# L_ftersteuerung.net
KiCad netlist of a schematic drawn in EAGLE
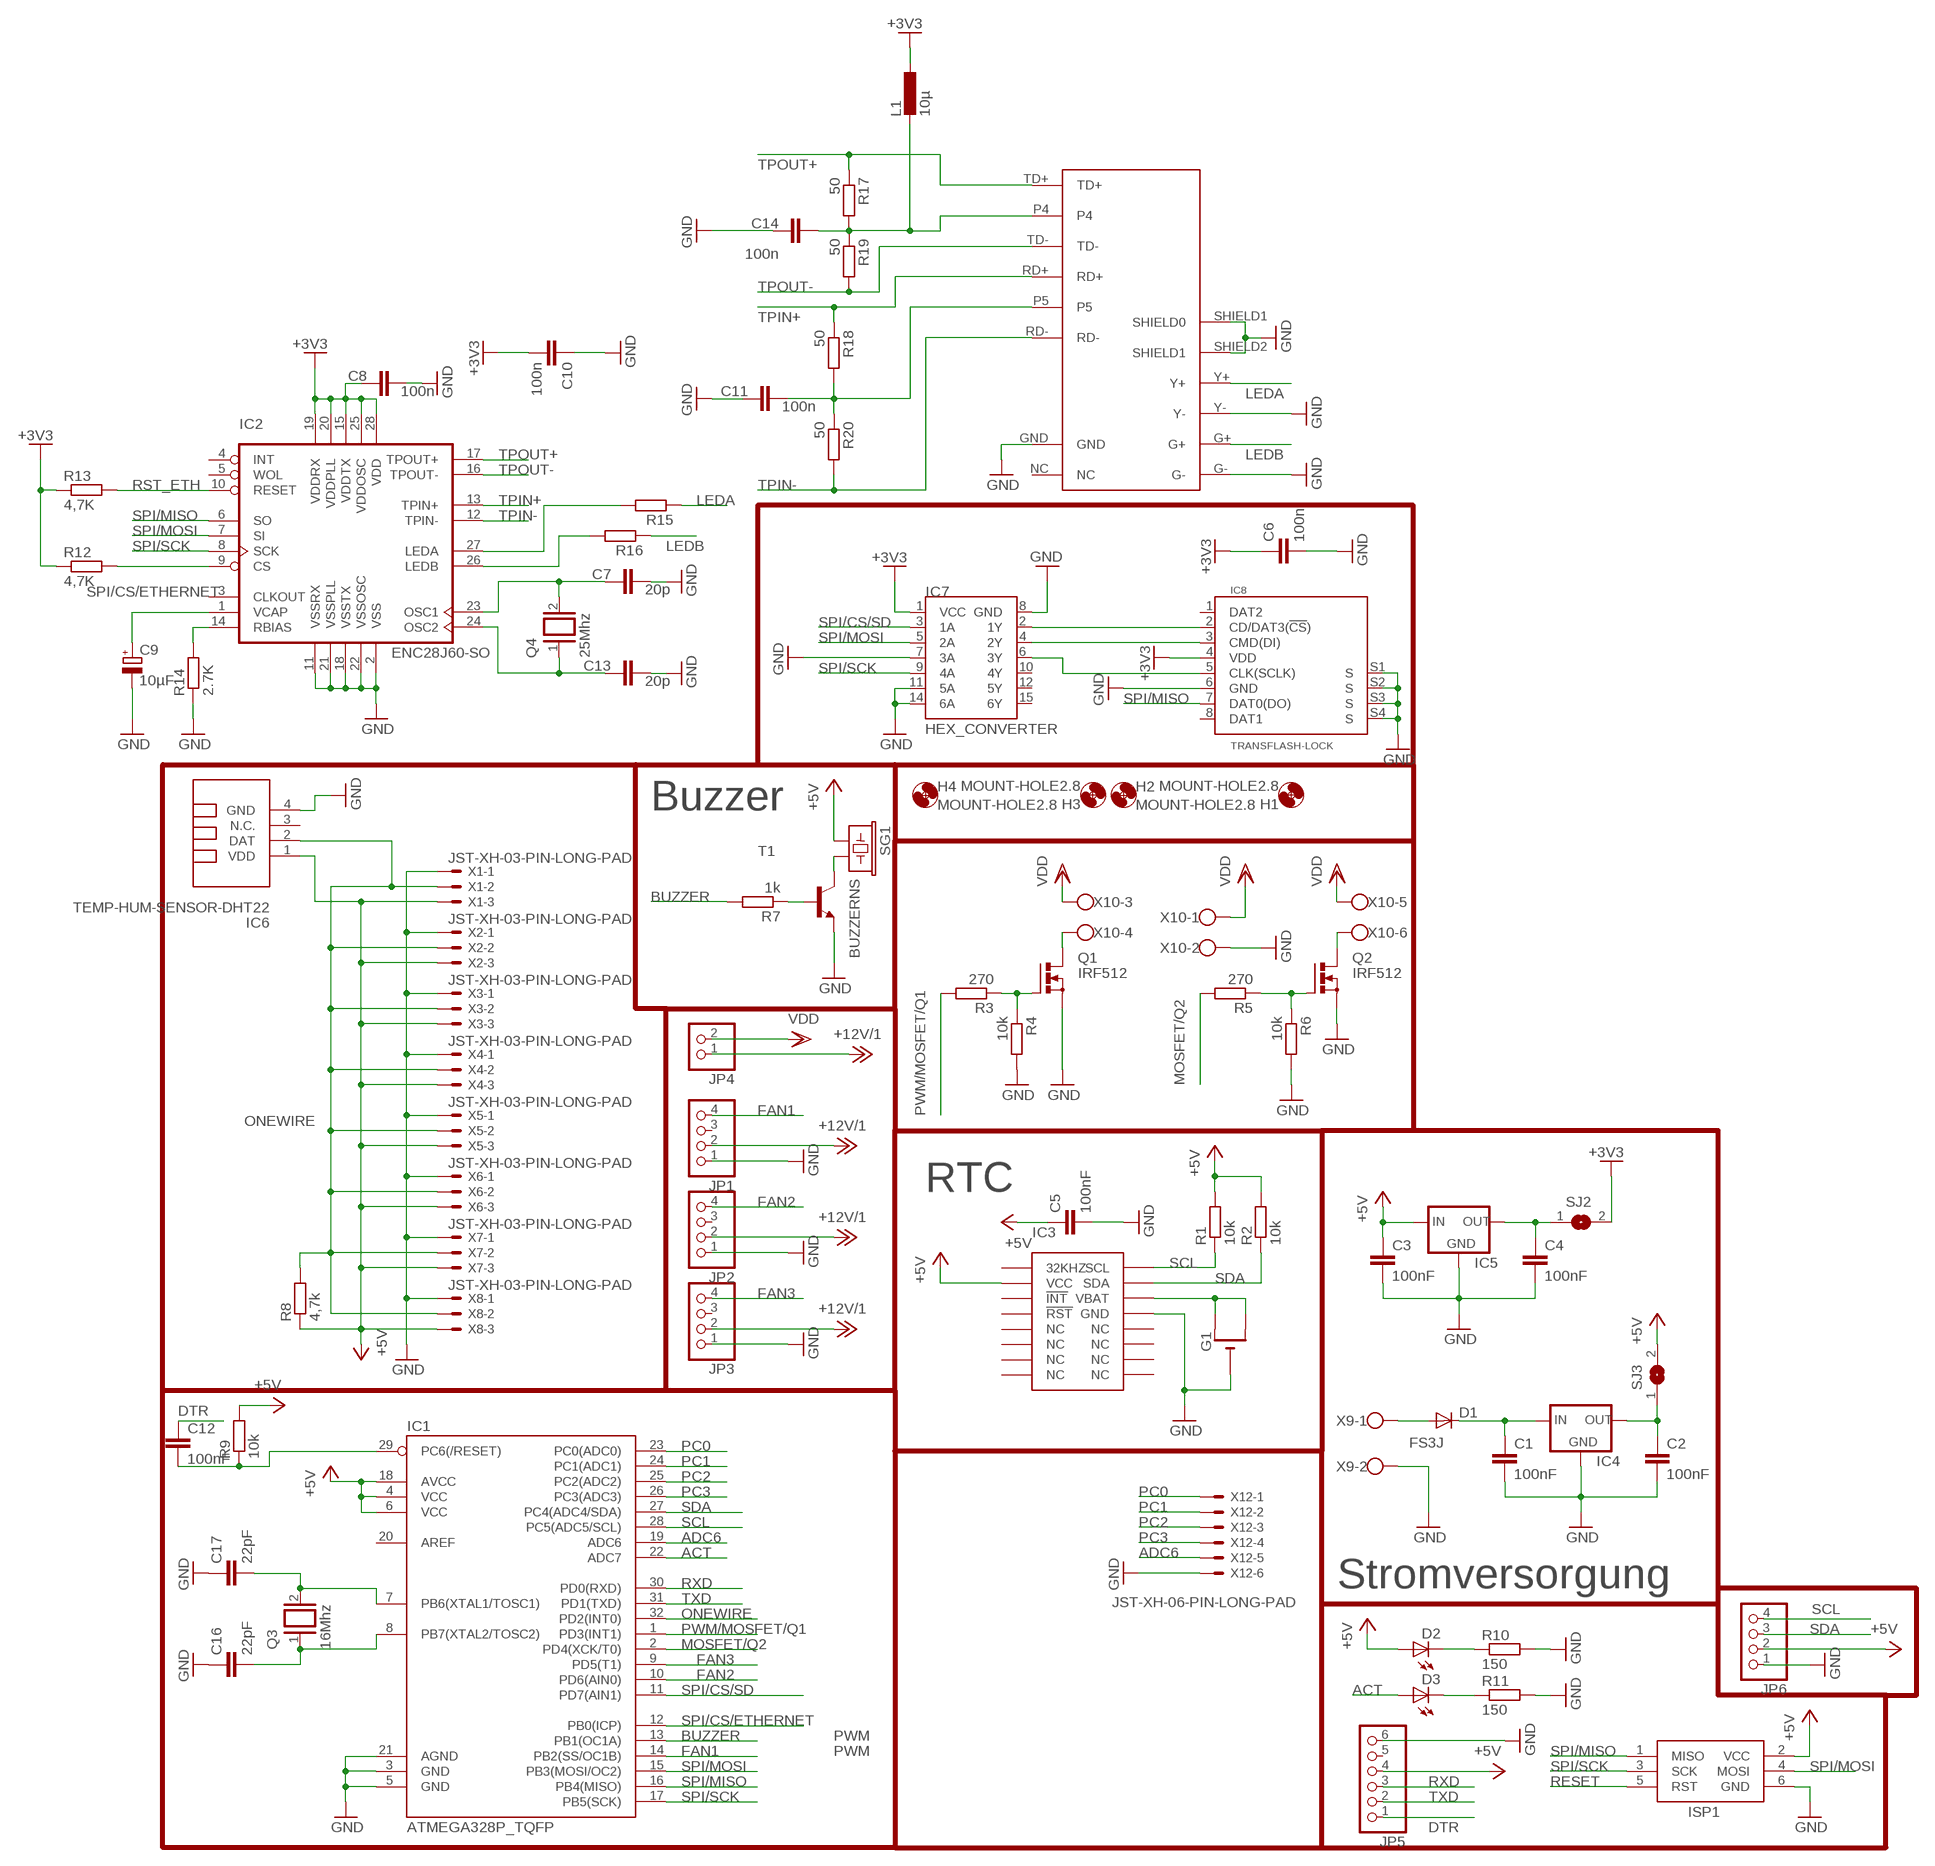
[diagram p0: schematic, sheet 1]

(export (version "E")
  (design (tool "Eeschema 10.0.6"))
  (components
    (comp (ref "C1")
      (value "100nF")
      (footprint "eagle-import:C1206")
      (libsource (lib "eagle-import") (part "C-EUC1206"))
    )
    (comp (ref "C2")
      (value "100nF")
      (footprint "eagle-import:C1206")
      (libsource (lib "eagle-import") (part "C-EUC1206"))
    )
    (comp (ref "C3")
      (value "100nF")
      (footprint "eagle-import:C1206")
      (libsource (lib "eagle-import") (part "C-EUC1206"))
    )
    (comp (ref "C4")
      (value "100nF")
      (footprint "eagle-import:C1206")
      (libsource (lib "eagle-import") (part "C-EUC1206"))
    )
    (comp (ref "C5")
      (value "100nF")
      (footprint "eagle-import:C1206")
      (libsource (lib "eagle-import") (part "C-EUC1206"))
    )
    (comp (ref "C6")
      (value "100n")
      (footprint "eagle-import:C1206")
      (libsource (lib "eagle-import") (part "C-EUC1206"))
    )
    (comp (ref "C7")
      (value "20p")
      (footprint "eagle-import:C1206")
      (libsource (lib "eagle-import") (part "C-EUC1206"))
    )
    (comp (ref "C8")
      (value "100n")
      (footprint "eagle-import:C1206")
      (libsource (lib "eagle-import") (part "C-EUC1206"))
    )
    (comp (ref "C9")
      (value "10µF")
      (footprint "eagle-import:A_3216-18W")
      (libsource (lib "eagle-import") (part "CPOL-EUA/3216-18W"))
    )
    (comp (ref "C10")
      (value "100n")
      (footprint "eagle-import:C1206")
      (libsource (lib "eagle-import") (part "C-EUC1206"))
    )
    (comp (ref "C11")
      (value "100n")
      (footprint "eagle-import:C1206")
      (libsource (lib "eagle-import") (part "C-EUC1206"))
    )
    (comp (ref "C12")
      (value "100nF")
      (footprint "eagle-import:C1206K")
      (libsource (lib "eagle-import") (part "C-EUC1206K"))
    )
    (comp (ref "C13")
      (value "20p")
      (footprint "eagle-import:C1206")
      (libsource (lib "eagle-import") (part "C-EUC1206"))
    )
    (comp (ref "C14")
      (value "100n")
      (footprint "eagle-import:C1206")
      (libsource (lib "eagle-import") (part "C-EUC1206"))
    )
    (comp (ref "C16")
      (value "22pF")
      (footprint "eagle-import:C1206K")
      (libsource (lib "eagle-import") (part "C-EUC1206K"))
    )
    (comp (ref "C17")
      (value "22pF")
      (footprint "eagle-import:C1206K")
      (libsource (lib "eagle-import") (part "C-EUC1206K"))
    )
    (comp (ref "D1")
      (value "FS3J")
      (footprint "eagle-import:SMC")
      (libsource (lib "eagle-import") (part "DIODE-SMC"))
    )
    (comp (ref "D2")
      (value "LED3MM")
      (footprint "eagle-import:LED3MM")
      (libsource (lib "eagle-import") (part "LED3MM"))
    )
    (comp (ref "D3")
      (value "LED3MM")
      (footprint "eagle-import:LED3MM")
      (libsource (lib "eagle-import") (part "LED3MM"))
    )
    (comp (ref "G1")
      (value "CR1220SMT")
      (footprint "eagle-import:CR1220-SMD")
      (libsource (lib "eagle-import") (part "CR1220SMT"))
    )
    (comp (ref "H1")
      (value "MOUNT-HOLE2.8")
      (footprint "eagle-import:2,8")
      (libsource (lib "eagle-import") (part "MOUNT-HOLE2.8"))
    )
    (comp (ref "H2")
      (value "MOUNT-HOLE2.8")
      (footprint "eagle-import:2,8")
      (libsource (lib "eagle-import") (part "MOUNT-HOLE2.8"))
    )
    (comp (ref "H3")
      (value "MOUNT-HOLE2.8")
      (footprint "eagle-import:2,8")
      (libsource (lib "eagle-import") (part "MOUNT-HOLE2.8"))
    )
    (comp (ref "H4")
      (value "MOUNT-HOLE2.8")
      (footprint "eagle-import:2,8")
      (libsource (lib "eagle-import") (part "MOUNT-HOLE2.8"))
    )
    (comp (ref "IC1")
      (value "ATMEGA328P_TQFP")
      (footprint "eagle-import:TQFP32-08")
      (libsource (lib "eagle-import") (part "ATMEGA328P_TQFP"))
    )
    (comp (ref "IC2")
      (value "ENC28J60-SO")
      (footprint "eagle-import:SO28W")
      (libsource (lib "eagle-import") (part "ENC28J60-SO"))
    )
    (comp (ref "IC3")
      (value "DS3231SOIC-16W")
      (footprint "eagle-import:SOIC-16W")
      (libsource (lib "eagle-import") (part "DS3231SOIC-16W"))
    )
    (comp (ref "IC4")
      (value "LM1117")
      (footprint "eagle-import:SOT223")
      (libsource (lib "eagle-import") (part "LM1117"))
    )
    (comp (ref "IC5")
      (value "LM1117")
      (footprint "eagle-import:SOT223")
      (libsource (lib "eagle-import") (part "LM1117"))
    )
    (comp (ref "IC6")
      (value "TEMP-HUM-SENSOR-DHT22")
      (footprint "eagle-import:TEMP-HUM-SENSOR-DHT22")
      (libsource (lib "eagle-import") (part "TEMP-HUM-SENSOR-DHT22"))
    )
    (comp (ref "IC7")
      (value "HEX_CONVERTER")
      (footprint "eagle-import:SO016")
      (libsource (lib "eagle-import") (part "HEX_CONVERTER"))
    )
    (comp (ref "IC8")
      (value "TRANSFLASH-LOCK")
      (footprint "eagle-import:TRANSFLASH-LOCK-SOCK")
      (libsource (lib "eagle-import") (part "TRANSFLASH-LOCK"))
    )
    (comp (ref "ISP1")
      (value "AVRISP-6")
      (footprint "eagle-import:AVRISP")
      (libsource (lib "eagle-import") (part "AVRISP-6"))
    )
    (comp (ref "JP1")
      (value "PINHD-1X4")
      (footprint "eagle-import:1X04")
      (libsource (lib "eagle-import") (part "PINHD-1X4"))
    )
    (comp (ref "JP2")
      (value "PINHD-1X4")
      (footprint "eagle-import:1X04")
      (libsource (lib "eagle-import") (part "PINHD-1X4"))
    )
    (comp (ref "JP3")
      (value "PINHD-1X4")
      (footprint "eagle-import:1X04")
      (libsource (lib "eagle-import") (part "PINHD-1X4"))
    )
    (comp (ref "JP4")
      (value "PINHD-1X2")
      (footprint "eagle-import:1X02")
      (libsource (lib "eagle-import") (part "PINHD-1X2"))
    )
    (comp (ref "JP5")
      (value "PINHD-1X6")
      (footprint "eagle-import:1X06")
      (libsource (lib "eagle-import") (part "PINHD-1X6"))
    )
    (comp (ref "JP6")
      (value "PINHD-1X4")
      (footprint "eagle-import:1X04")
      (libsource (lib "eagle-import") (part "PINHD-1X4"))
    )
    (comp (ref "L1")
      (value "10µ")
      (footprint "eagle-import:L0805")
      (libsource (lib "eagle-import") (part "L-EUL0805"))
    )
    (comp (ref "Q1")
      (value "IRF512")
      (footprint "eagle-import:TO220BV")
      (libsource (lib "eagle-import") (part "IRF512"))
    )
    (comp (ref "Q2")
      (value "IRF512")
      (footprint "eagle-import:TO220BV")
      (libsource (lib "eagle-import") (part "IRF512"))
    )
    (comp (ref "Q3")
      (value "16Mhz")
      (footprint "eagle-import:QS")
      (libsource (lib "eagle-import") (part "XTAL/S"))
    )
    (comp (ref "Q4")
      (value "25Mhz")
      (footprint "eagle-import:QS")
      (libsource (lib "eagle-import") (part "XTAL/S"))
    )
    (comp (ref "R1")
      (value "10k")
      (footprint "eagle-import:R1206")
      (libsource (lib "eagle-import") (part "R-EU_R1206"))
    )
    (comp (ref "R2")
      (value "10k")
      (footprint "eagle-import:R1206")
      (libsource (lib "eagle-import") (part "R-EU_R1206"))
    )
    (comp (ref "R3")
      (value "270")
      (footprint "eagle-import:R1206")
      (libsource (lib "eagle-import") (part "R-EU_R1206"))
    )
    (comp (ref "R4")
      (value "10k")
      (footprint "eagle-import:R1206")
      (libsource (lib "eagle-import") (part "R-EU_R1206"))
    )
    (comp (ref "R5")
      (value "270")
      (footprint "eagle-import:R1206")
      (libsource (lib "eagle-import") (part "R-EU_R1206"))
    )
    (comp (ref "R6")
      (value "10k")
      (footprint "eagle-import:R1206")
      (libsource (lib "eagle-import") (part "R-EU_R1206"))
    )
    (comp (ref "R7")
      (value "1k")
      (footprint "eagle-import:R1206")
      (libsource (lib "eagle-import") (part "R-EU_R1206"))
    )
    (comp (ref "R8")
      (value "4,7k")
      (footprint "eagle-import:R1206")
      (libsource (lib "eagle-import") (part "R-EU_R1206"))
    )
    (comp (ref "R9")
      (value "10k")
      (footprint "eagle-import:M1206")
      (libsource (lib "eagle-import") (part "R-EU_M1206"))
    )
    (comp (ref "R10")
      (value "150")
      (footprint "eagle-import:M1206")
      (libsource (lib "eagle-import") (part "R-EU_M1206"))
    )
    (comp (ref "R11")
      (value "150")
      (footprint "eagle-import:M1206")
      (libsource (lib "eagle-import") (part "R-EU_M1206"))
    )
    (comp (ref "R12")
      (value "4,7K")
      (footprint "eagle-import:R1206")
      (libsource (lib "eagle-import") (part "R-EU_R1206"))
    )
    (comp (ref "R13")
      (value "4,7K")
      (footprint "eagle-import:R1206")
      (libsource (lib "eagle-import") (part "R-EU_R1206"))
    )
    (comp (ref "R14")
      (value "2.7K")
      (footprint "eagle-import:R1206")
      (libsource (lib "eagle-import") (part "R-EU_R1206"))
    )
    (comp (ref "R15")
      (value "R-EU_R1206")
      (footprint "eagle-import:R1206")
      (libsource (lib "eagle-import") (part "R-EU_R1206"))
    )
    (comp (ref "R16")
      (value "R-EU_R1206")
      (footprint "eagle-import:R1206")
      (libsource (lib "eagle-import") (part "R-EU_R1206"))
    )
    (comp (ref "R17")
      (value "50")
      (footprint "eagle-import:R1206")
      (libsource (lib "eagle-import") (part "R-EU_R1206"))
    )
    (comp (ref "R18")
      (value "50")
      (footprint "eagle-import:R1206")
      (libsource (lib "eagle-import") (part "R-EU_R1206"))
    )
    (comp (ref "R19")
      (value "50")
      (footprint "eagle-import:R1206")
      (libsource (lib "eagle-import") (part "R-EU_R1206"))
    )
    (comp (ref "R20")
      (value "50")
      (footprint "eagle-import:R1206")
      (libsource (lib "eagle-import") (part "R-EU_R1206"))
    )
    (comp (ref "SG1")
      (value "BUZZERNS")
      (footprint "eagle-import:BUZZER-12MM-NS")
      (libsource (lib "eagle-import") (part "BUZZERNS"))
    )
    (comp (ref "SJ2") (value "SJ") (footprint "eagle-import:SJ") (libsource (lib "eagle-import") (part "SJ")))
    (comp (ref "SJ3") (value "SJ") (footprint "eagle-import:SJ") (libsource (lib "eagle-import") (part "SJ")))
    (comp (ref "T1")
      (value "BC817-16-NPN-SOT23-BEC")
      (footprint "eagle-import:SOT23-BEC")
      (libsource (lib "eagle-import") (part "-NPN-SOT23-BECBC817-16"))
    )
    (comp (ref "U$1")
      (value "HR911105A")
      (footprint "eagle-import:RJ45")
      (libsource (lib "eagle-import") (part "HR911105A"))
    )
    (comp (ref "X1")
      (value "JST-XH-03-PIN-LONG-PAD")
      (footprint "eagle-import:JST-XH-03-PACKAGE-LONG-PAD")
      (libsource (lib "eagle-import") (part "JST-XH-03-PIN-LONG-PAD"))
    )
    (comp (ref "X2")
      (value "JST-XH-03-PIN-LONG-PAD")
      (footprint "eagle-import:JST-XH-03-PACKAGE-LONG-PAD")
      (libsource (lib "eagle-import") (part "JST-XH-03-PIN-LONG-PAD"))
    )
    (comp (ref "X3")
      (value "JST-XH-03-PIN-LONG-PAD")
      (footprint "eagle-import:JST-XH-03-PACKAGE-LONG-PAD")
      (libsource (lib "eagle-import") (part "JST-XH-03-PIN-LONG-PAD"))
    )
    (comp (ref "X4")
      (value "JST-XH-03-PIN-LONG-PAD")
      (footprint "eagle-import:JST-XH-03-PACKAGE-LONG-PAD")
      (libsource (lib "eagle-import") (part "JST-XH-03-PIN-LONG-PAD"))
    )
    (comp (ref "X5")
      (value "JST-XH-03-PIN-LONG-PAD")
      (footprint "eagle-import:JST-XH-03-PACKAGE-LONG-PAD")
      (libsource (lib "eagle-import") (part "JST-XH-03-PIN-LONG-PAD"))
    )
    (comp (ref "X6")
      (value "JST-XH-03-PIN-LONG-PAD")
      (footprint "eagle-import:JST-XH-03-PACKAGE-LONG-PAD")
      (libsource (lib "eagle-import") (part "JST-XH-03-PIN-LONG-PAD"))
    )
    (comp (ref "X7")
      (value "JST-XH-03-PIN-LONG-PAD")
      (footprint "eagle-import:JST-XH-03-PACKAGE-LONG-PAD")
      (libsource (lib "eagle-import") (part "JST-XH-03-PIN-LONG-PAD"))
    )
    (comp (ref "X8")
      (value "JST-XH-03-PIN-LONG-PAD")
      (footprint "eagle-import:JST-XH-03-PACKAGE-LONG-PAD")
      (libsource (lib "eagle-import") (part "JST-XH-03-PIN-LONG-PAD"))
    )
    (comp (ref "X9")
      (value "W237-102")
      (footprint "eagle-import:W237-102")
      (libsource (lib "eagle-import") (part "W237-102"))
    )
    (comp (ref "X10")
      (value "W237-6")
      (footprint "eagle-import:W237-6")
      (libsource (lib "eagle-import") (part "W237-6"))
    )
    (comp (ref "X12")
      (value "JST-XH-06-PIN-LONG-PAD")
      (footprint "eagle-import:JST-XH-06-PACKAGE-LONG-PAD")
      (libsource (lib "eagle-import") (part "JST-XH-06-PIN-LONG-PAD"))
    )
  )
  (nets
    (net (code "1") (name "+3V3") (class "Default")
      (node (ref "C10") (pin "2") (pinfunction "2_2") (pintype "passive"))
      (node (ref "C6") (pin "1") (pinfunction "1_1") (pintype "passive"))
      (node (ref "C8") (pin "1") (pinfunction "1_1") (pintype "passive"))
      (node (ref "IC2") (pin "15") (pinfunction "VDDTX_15") (pintype "power_in"))
      (node (ref "IC2") (pin "19") (pinfunction "VDDRX_19") (pintype "power_in"))
      (node (ref "IC2") (pin "20") (pinfunction "VDDPLL_20") (pintype "power_in"))
      (node (ref "IC2") (pin "25") (pinfunction "VDDOSC_25") (pintype "power_in"))
      (node (ref "IC2") (pin "28") (pinfunction "VDD_28") (pintype "power_in"))
      (node (ref "IC7") (pin "1") (pinfunction "VCC_1") (pintype "bidirectional"))
      (node (ref "IC8") (pin "4") (pinfunction "VDD_4") (pintype "power_in"))
      (node (ref "L1") (pin "1") (pinfunction "1_1") (pintype "passive"))
      (node (ref "R12") (pin "1") (pinfunction "1_1") (pintype "passive"))
      (node (ref "R13") (pin "1") (pinfunction "1_1") (pintype "passive"))
      (node (ref "SJ2") (pin "2") (pinfunction "2_2") (pintype "passive"))
    )
    (net (code "2") (name "+5V") (class "Default")
      (node (ref "C3") (pin "1") (pinfunction "1_1") (pintype "passive"))
      (node (ref "C5") (pin "1") (pinfunction "1_1") (pintype "passive"))
      (node (ref "D2") (pin "A") (pinfunction "A_A") (pintype "passive"))
      (node (ref "IC1") (pin "18") (pinfunction "AVCC_18") (pintype "bidirectional"))
      (node (ref "IC1") (pin "4") (pinfunction "VCC_4") (pintype "bidirectional"))
      (node (ref "IC1") (pin "6") (pinfunction "VCC_6") (pintype "bidirectional"))
      (node (ref "IC3") (pin "2") (pinfunction "VCC_2") (pintype "bidirectional"))
      (node (ref "IC5") (pin "3") (pinfunction "IN_3") (pintype "input"))
      (node (ref "IC6") (pin "1") (pinfunction "VDD_1") (pintype "power_in"))
      (node (ref "ISP1") (pin "2") (pinfunction "VCC_2") (pintype "power_in"))
      (node (ref "JP5") (pin "4") (pinfunction "4_4") (pintype "passive"))
      (node (ref "JP6") (pin "2") (pinfunction "2_2") (pintype "passive"))
      (node (ref "R1") (pin "2") (pinfunction "2_2") (pintype "passive"))
      (node (ref "R2") (pin "2") (pinfunction "2_2") (pintype "passive"))
      (node (ref "R8") (pin "1") (pinfunction "1_1") (pintype "passive"))
      (node (ref "R9") (pin "2") (pinfunction "2_2") (pintype "passive"))
      (node (ref "SG1") (pin "+") (pinfunction "1_+") (pintype "passive"))
      (node (ref "SJ3") (pin "2") (pinfunction "2_2") (pintype "passive"))
      (node (ref "X1") (pin "3") (pinfunction "S_3") (pintype "passive"))
      (node (ref "X2") (pin "3") (pinfunction "S_3") (pintype "passive"))
      (node (ref "X3") (pin "3") (pinfunction "S_3") (pintype "passive"))
      (node (ref "X4") (pin "3") (pinfunction "S_3") (pintype "passive"))
      (node (ref "X5") (pin "3") (pinfunction "S_3") (pintype "passive"))
      (node (ref "X6") (pin "3") (pinfunction "S_3") (pintype "passive"))
      (node (ref "X7") (pin "3") (pinfunction "S_3") (pintype "passive"))
      (node (ref "X8") (pin "3") (pinfunction "S_3") (pintype "passive"))
    )
    (net (code "3") (name "+12V{slash}1") (class "Default")
      (node (ref "JP1") (pin "2") (pinfunction "2_2") (pintype "passive"))
      (node (ref "JP2") (pin "2") (pinfunction "2_2") (pintype "passive"))
      (node (ref "JP3") (pin "2") (pinfunction "2_2") (pintype "passive"))
      (node (ref "JP4") (pin "1") (pinfunction "1_1") (pintype "passive"))
    )
    (net (code "4") (name "/ACT") (class "Default")
      (node (ref "D3") (pin "A") (pinfunction "A_A") (pintype "passive"))
      (node (ref "IC1") (pin "22") (pinfunction "ADC7_22") (pintype "bidirectional"))
    )
    (net (code "5") (name "/ADC6") (class "Default")
      (node (ref "IC1") (pin "19") (pinfunction "ADC6_19") (pintype "bidirectional"))
      (node (ref "X12") (pin "5") (pinfunction "S_5") (pintype "passive"))
    )
    (net (code "6") (name "/BUZZER") (class "Default")
      (node (ref "IC1") (pin "13") (pinfunction "PB1(OC1A)_13") (pintype "bidirectional"))
      (node (ref "R7") (pin "2") (pinfunction "2_2") (pintype "passive"))
    )
    (net (code "7") (name "/DTR") (class "Default")
      (node (ref "C12") (pin "1") (pinfunction "1_1") (pintype "passive"))
      (node (ref "JP5") (pin "1") (pinfunction "1_1") (pintype "passive"))
    )
    (net (code "8") (name "/FAN1") (class "Default")
      (node (ref "IC1") (pin "14") (pinfunction "PB2(SS/OC1B)_14") (pintype "bidirectional"))
      (node (ref "JP1") (pin "4") (pinfunction "4_4") (pintype "passive"))
    )
    (net (code "9") (name "/FAN2") (class "Default")
      (node (ref "IC1") (pin "10") (pinfunction "PD6(AIN0)_10") (pintype "bidirectional"))
      (node (ref "JP2") (pin "4") (pinfunction "4_4") (pintype "passive"))
    )
    (net (code "10") (name "/FAN3") (class "Default")
      (node (ref "IC1") (pin "9") (pinfunction "PD5(T1)_9") (pintype "bidirectional"))
      (node (ref "JP3") (pin "4") (pinfunction "4_4") (pintype "passive"))
    )
    (net (code "11") (name "/LEDA") (class "Default")
      (node (ref "R15") (pin "1") (pinfunction "1_1") (pintype "passive"))
      (node (ref "U$1") (pin "Y+") (pinfunction "Y+_Y+") (pintype "bidirectional"))
    )
    (net (code "12") (name "/LEDB") (class "Default")
      (node (ref "R16") (pin "1") (pinfunction "1_1") (pintype "passive"))
      (node (ref "U$1") (pin "G+") (pinfunction "G+_G+") (pintype "bidirectional"))
    )
    (net (code "13") (name "/MOSFET{slash}Q2") (class "Default")
      (node (ref "IC1") (pin "2") (pinfunction "PD4(XCK/T0)_2") (pintype "bidirectional"))
      (node (ref "R5") (pin "2") (pinfunction "2_2") (pintype "passive"))
    )
    (net (code "14") (name "/ONEWIRE") (class "Default")
      (node (ref "IC1") (pin "32") (pinfunction "PD2(INT0)_32") (pintype "bidirectional"))
      (node (ref "IC6") (pin "2") (pinfunction "DAT_2") (pintype "bidirectional"))
      (node (ref "R8") (pin "2") (pinfunction "2_2") (pintype "passive"))
      (node (ref "X1") (pin "2") (pinfunction "S_2") (pintype "passive"))
      (node (ref "X2") (pin "2") (pinfunction "S_2") (pintype "passive"))
      (node (ref "X3") (pin "2") (pinfunction "S_2") (pintype "passive"))
      (node (ref "X4") (pin "2") (pinfunction "S_2") (pintype "passive"))
      (node (ref "X5") (pin "2") (pinfunction "S_2") (pintype "passive"))
      (node (ref "X6") (pin "2") (pinfunction "S_2") (pintype "passive"))
      (node (ref "X7") (pin "2") (pinfunction "S_2") (pintype "passive"))
      (node (ref "X8") (pin "2") (pinfunction "S_2") (pintype "passive"))
    )
    (net (code "15") (name "/PC0") (class "Default")
      (node (ref "IC1") (pin "23") (pinfunction "PC0(ADC0)_23") (pintype "bidirectional"))
      (node (ref "X12") (pin "1") (pinfunction "S_1") (pintype "passive"))
    )
    (net (code "16") (name "/PC1") (class "Default")
      (node (ref "IC1") (pin "24") (pinfunction "PC1(ADC1)_24") (pintype "bidirectional"))
      (node (ref "X12") (pin "2") (pinfunction "S_2") (pintype "passive"))
    )
    (net (code "17") (name "/PC2") (class "Default")
      (node (ref "IC1") (pin "25") (pinfunction "PC2(ADC2)_25") (pintype "bidirectional"))
      (node (ref "X12") (pin "3") (pinfunction "S_3") (pintype "passive"))
    )
    (net (code "18") (name "/PC3") (class "Default")
      (node (ref "IC1") (pin "26") (pinfunction "PC3(ADC3)_26") (pintype "bidirectional"))
      (node (ref "X12") (pin "4") (pinfunction "S_4") (pintype "passive"))
    )
    (net (code "19") (name "/PWM{slash}MOSFET{slash}Q1") (class "Default")
      (node (ref "IC1") (pin "1") (pinfunction "PD3(INT1)_1") (pintype "bidirectional"))
      (node (ref "R3") (pin "2") (pinfunction "2_2") (pintype "passive"))
    )
    (net (code "20") (name "/RESET") (class "Default")
      (node (ref "C12") (pin "2") (pinfunction "2_2") (pintype "passive"))
      (node (ref "IC1") (pin "29") (pinfunction "PC6(/RESET)_29") (pintype "bidirectional"))
      (node (ref "ISP1") (pin "5") (pinfunction "RST_5") (pintype "output"))
      (node (ref "R9") (pin "1") (pinfunction "1_1") (pintype "passive"))
    )
    (net (code "21") (name "/RST_ETH") (class "Default")
      (node (ref "IC2") (pin "10") (pinfunction "RESET_10") (pintype "input"))
      (node (ref "R13") (pin "2") (pinfunction "2_2") (pintype "passive"))
    )
    (net (code "22") (name "/RXD") (class "Default")
      (node (ref "IC1") (pin "30") (pinfunction "PD0(RXD)_30") (pintype "bidirectional"))
      (node (ref "JP5") (pin "3") (pinfunction "3_3") (pintype "passive"))
    )
    (net (code "23") (name "/SCL") (class "Default")
      (node (ref "IC1") (pin "28") (pinfunction "PC5(ADC5/SCL)_28") (pintype "bidirectional"))
      (node (ref "IC3") (pin "16") (pinfunction "SCL_16") (pintype "bidirectional"))
      (node (ref "JP6") (pin "4") (pinfunction "4_4") (pintype "passive"))
      (node (ref "R1") (pin "1") (pinfunction "1_1") (pintype "passive"))
    )
    (net (code "24") (name "/SDA") (class "Default")
      (node (ref "IC1") (pin "27") (pinfunction "PC4(ADC4/SDA)_27") (pintype "bidirectional"))
      (node (ref "IC3") (pin "15") (pinfunction "SDA_15") (pintype "bidirectional"))
      (node (ref "JP6") (pin "3") (pinfunction "3_3") (pintype "passive"))
      (node (ref "R2") (pin "1") (pinfunction "1_1") (pintype "passive"))
    )
    (net (code "25") (name "/SPI{slash}CS{slash}ETHERNET") (class "Default")
      (node (ref "IC1") (pin "12") (pinfunction "PB0(ICP)_12") (pintype "bidirectional"))
      (node (ref "IC2") (pin "9") (pinfunction "CS_9") (pintype "input"))
      (node (ref "R12") (pin "2") (pinfunction "2_2") (pintype "passive"))
    )
    (net (code "26") (name "/SPI{slash}CS{slash}SD") (class "Default")
      (node (ref "IC1") (pin "11") (pinfunction "PD7(AIN1)_11") (pintype "bidirectional"))
      (node (ref "IC7") (pin "3") (pinfunction "1A_3") (pintype "bidirectional"))
    )
    (net (code "27") (name "/SPI{slash}MISO") (class "Default")
      (node (ref "IC1") (pin "16") (pinfunction "PB4(MISO)_16") (pintype "bidirectional"))
      (node (ref "IC2") (pin "6") (pinfunction "SO_6") (pintype "output"))
      (node (ref "IC8") (pin "7") (pinfunction "DAT0(DO)_7") (pintype "bidirectional"))
      (node (ref "ISP1") (pin "1") (pinfunction "MISO_1") (pintype "input"))
    )
    (net (code "28") (name "/SPI{slash}MOSI") (class "Default")
      (node (ref "IC1") (pin "15") (pinfunction "PB3(MOSI/OC2)_15") (pintype "bidirectional"))
      (node (ref "IC2") (pin "7") (pinfunction "SI_7") (pintype "input"))
      (node (ref "IC7") (pin "5") (pinfunction "2A_5") (pintype "bidirectional"))
      (node (ref "ISP1") (pin "4") (pinfunction "MOSI_4") (pintype "output"))
    )
    (net (code "29") (name "/SPI{slash}SCK") (class "Default")
      (node (ref "IC1") (pin "17") (pinfunction "PB5(SCK)_17") (pintype "bidirectional"))
      (node (ref "IC2") (pin "8") (pinfunction "SCK_8") (pintype "input"))
      (node (ref "IC7") (pin "9") (pinfunction "4A_9") (pintype "bidirectional"))
      (node (ref "ISP1") (pin "3") (pinfunction "SCK_3") (pintype "output"))
    )
    (net (code "30") (name "/TPIN+") (class "Default")
      (node (ref "IC2") (pin "13") (pinfunction "TPIN+_13") (pintype "input"))
      (node (ref "R18") (pin "1") (pinfunction "1_1") (pintype "passive"))
      (node (ref "U$1") (pin "RD+") (pinfunction "RD+_RD+") (pintype "bidirectional"))
    )
    (net (code "31") (name "/TPIN-") (class "Default")
      (node (ref "IC2") (pin "12") (pinfunction "TPIN-_12") (pintype "input"))
      (node (ref "R20") (pin "2") (pinfunction "2_2") (pintype "passive"))
      (node (ref "U$1") (pin "RD-") (pinfunction "RD-_RD-") (pintype "bidirectional"))
    )
    (net (code "32") (name "/TPOUT+") (class "Default")
      (node (ref "IC2") (pin "17") (pinfunction "TPOUT+_17") (pintype "output"))
      (node (ref "R17") (pin "1") (pinfunction "1_1") (pintype "passive"))
      (node (ref "U$1") (pin "TD+") (pinfunction "TD+_TD+") (pintype "bidirectional"))
    )
    (net (code "33") (name "/TPOUT-") (class "Default")
      (node (ref "IC2") (pin "16") (pinfunction "TPOUT-_16") (pintype "output"))
      (node (ref "R19") (pin "2") (pinfunction "2_2") (pintype "passive"))
      (node (ref "U$1") (pin "TD-") (pinfunction "TD-_TD-") (pintype "bidirectional"))
    )
    (net (code "34") (name "/TXD") (class "Default")
      (node (ref "IC1") (pin "31") (pinfunction "PD1(TXD)_31") (pintype "bidirectional"))
      (node (ref "JP5") (pin "2") (pinfunction "2_2") (pintype "passive"))
    )
    (net (code "35") (name "GND") (class "Default")
      (node (ref "C1") (pin "2") (pinfunction "2_2") (pintype "passive"))
      (node (ref "C10") (pin "1") (pinfunction "1_1") (pintype "passive"))
      (node (ref "C11") (pin "1") (pinfunction "1_1") (pintype "passive"))
      (node (ref "C13") (pin "1") (pinfunction "1_1") (pintype "passive"))
      (node (ref "C14") (pin "1") (pinfunction "1_1") (pintype "passive"))
      (node (ref "C16") (pin "1") (pinfunction "1_1") (pintype "passive"))
      (node (ref "C17") (pin "1") (pinfunction "1_1") (pintype "passive"))
      (node (ref "C2") (pin "2") (pinfunction "2_2") (pintype "passive"))
      (node (ref "C3") (pin "2") (pinfunction "2_2") (pintype "passive"))
      (node (ref "C4") (pin "2") (pinfunction "2_2") (pintype "passive"))
      (node (ref "C5") (pin "2") (pinfunction "2_2") (pintype "passive"))
      (node (ref "C6") (pin "2") (pinfunction "2_2") (pintype "passive"))
      (node (ref "C7") (pin "2") (pinfunction "2_2") (pintype "passive"))
      (node (ref "C8") (pin "2") (pinfunction "2_2") (pintype "passive"))
      (node (ref "C9") (pin "-") (pinfunction "-_-") (pintype "passive"))
      (node (ref "G1") (pin "-") (pinfunction "-_-") (pintype "passive"))
      (node (ref "IC1") (pin "21") (pinfunction "AGND_21") (pintype "bidirectional"))
      (node (ref "IC1") (pin "3") (pinfunction "GND_3") (pintype "bidirectional"))
      (node (ref "IC1") (pin "5") (pinfunction "GND_5") (pintype "bidirectional"))
      (node (ref "IC2") (pin "11") (pinfunction "VSSRX_11") (pintype "power_in"))
      (node (ref "IC2") (pin "18") (pinfunction "VSSTX_18") (pintype "power_in"))
      (node (ref "IC2") (pin "2") (pinfunction "VSS_2") (pintype "power_in"))
      (node (ref "IC2") (pin "21") (pinfunction "VSSPLL_21") (pintype "power_in"))
      (node (ref "IC2") (pin "22") (pinfunction "VSSOSC_22") (pintype "power_in"))
      (node (ref "IC3") (pin "13") (pinfunction "GND_13") (pintype "bidirectional"))
      (node (ref "IC4") (pin "1") (pinfunction "GND_1") (pintype "input"))
      (node (ref "IC5") (pin "1") (pinfunction "GND_1") (pintype "input"))
      (node (ref "IC6") (pin "4") (pinfunction "GND_4") (pintype "power_in"))
      (node (ref "IC7") (pin "11") (pinfunction "5A_11") (pintype "bidirectional"))
      (node (ref "IC7") (pin "14") (pinfunction "6A_14") (pintype "bidirectional"))
      (node (ref "IC7") (pin "7") (pinfunction "3A_7") (pintype "bidirectional"))
      (node (ref "IC7") (pin "8") (pinfunction "GND_8") (pintype "bidirectional"))
      (node (ref "IC8") (pin "6") (pinfunction "GND_6") (pintype "power_in"))
      (node (ref "IC8") (pin "S1") (pinfunction "S_S1") (pintype "passive"))
      (node (ref "IC8") (pin "S2") (pinfunction "S_S2") (pintype "passive"))
      (node (ref "IC8") (pin "S3") (pinfunction "S_S3") (pintype "passive"))
      (node (ref "IC8") (pin "S4") (pinfunction "S_S4") (pintype "passive"))
      (node (ref "ISP1") (pin "6") (pinfunction "GND_6") (pintype "power_in"))
      (node (ref "JP1") (pin "1") (pinfunction "1_1") (pintype "passive"))
      (node (ref "JP2") (pin "1") (pinfunction "1_1") (pintype "passive"))
      (node (ref "JP3") (pin "1") (pinfunction "1_1") (pintype "passive"))
      (node (ref "JP5") (pin "6") (pinfunction "6_6") (pintype "passive"))
      (node (ref "JP6") (pin "1") (pinfunction "1_1") (pintype "passive"))
      (node (ref "Q1") (pin "S") (pinfunction "S_S") (pintype "passive"))
      (node (ref "Q2") (pin "S") (pinfunction "S_S") (pintype "passive"))
      (node (ref "R10") (pin "2") (pinfunction "2_2") (pintype "passive"))
      (node (ref "R11") (pin "2") (pinfunction "2_2") (pintype "passive"))
      (node (ref "R14") (pin "1") (pinfunction "1_1") (pintype "passive"))
      (node (ref "R4") (pin "2") (pinfunction "2_2") (pintype "passive"))
      (node (ref "R6") (pin "2") (pinfunction "2_2") (pintype "passive"))
      (node (ref "T1") (pin "E") (pinfunction "E_E") (pintype "passive"))
      (node (ref "U$1") (pin "G-") (pinfunction "G-_G-") (pintype "bidirectional"))
      (node (ref "U$1") (pin "GND") (pinfunction "GND_GND") (pintype "bidirectional"))
      (node (ref "U$1") (pin "SHIELD1") (pinfunction "SHIELD0_SHIELD1") (pintype "bidirectional"))
      (node (ref "U$1") (pin "SHIELD2") (pinfunction "SHIELD1_SHIELD2") (pintype "bidirectional"))
      (node (ref "U$1") (pin "Y-") (pinfunction "Y-_Y-") (pintype "bidirectional"))
      (node (ref "X1") (pin "1") (pinfunction "S_1") (pintype "passive"))
      (node (ref "X10") (pin "2") (pinfunction "KL_2") (pintype "passive"))
      (node (ref "X12") (pin "6") (pinfunction "S_6") (pintype "passive"))
      (node (ref "X2") (pin "1") (pinfunction "S_1") (pintype "passive"))
      (node (ref "X3") (pin "1") (pinfunction "S_1") (pintype "passive"))
      (node (ref "X4") (pin "1") (pinfunction "S_1") (pintype "passive"))
      (node (ref "X5") (pin "1") (pinfunction "S_1") (pintype "passive"))
      (node (ref "X6") (pin "1") (pinfunction "S_1") (pintype "passive"))
      (node (ref "X7") (pin "1") (pinfunction "S_1") (pintype "passive"))
      (node (ref "X8") (pin "1") (pinfunction "S_1") (pintype "passive"))
      (node (ref "X9") (pin "2") (pinfunction "KL_2") (pintype "passive"))
    )
    (net (code "36") (name "Net-(C11-Pad2)") (class "Default")
      (node (ref "C11") (pin "2") (pinfunction "2_2") (pintype "passive"))
      (node (ref "R18") (pin "2") (pinfunction "2_2") (pintype "passive"))
      (node (ref "R20") (pin "1") (pinfunction "1_1") (pintype "passive"))
      (node (ref "U$1") (pin "P5") (pinfunction "P5_P5") (pintype "bidirectional"))
    )
    (net (code "37") (name "Net-(C14-Pad2)") (class "Default")
      (node (ref "C14") (pin "2") (pinfunction "2_2") (pintype "passive"))
      (node (ref "L1") (pin "2") (pinfunction "2_2") (pintype "passive"))
      (node (ref "R17") (pin "2") (pinfunction "2_2") (pintype "passive"))
      (node (ref "R19") (pin "1") (pinfunction "1_1") (pintype "passive"))
      (node (ref "U$1") (pin "P4") (pinfunction "P4_P4") (pintype "bidirectional"))
    )
    (net (code "38") (name "Net-(D2-C)") (class "Default")
      (node (ref "D2") (pin "K") (pinfunction "C_K") (pintype "passive"))
      (node (ref "R10") (pin "1") (pinfunction "1_1") (pintype "passive"))
    )
    (net (code "39") (name "Net-(D3-C)") (class "Default")
      (node (ref "D3") (pin "K") (pinfunction "C_K") (pintype "passive"))
      (node (ref "R11") (pin "1") (pinfunction "1_1") (pintype "passive"))
    )
    (net (code "40") (name "Net-(G1-+)") (class "Default")
      (node (ref "G1") (pin "+$1") (pinfunction "+_+$1") (pintype "passive"))
      (node (ref "G1") (pin "+$2") (pinfunction "+1_+$2") (pintype "passive"))
      (node (ref "IC3") (pin "14") (pinfunction "VBAT_14") (pintype "bidirectional"))
    )
    (net (code "41") (name "Net-(IC1-PB6(XTAL1{slash}TOSC1))") (class "Default")
      (node (ref "C17") (pin "2") (pinfunction "2_2") (pintype "passive"))
      (node (ref "IC1") (pin "7") (pinfunction "PB6(XTAL1/TOSC1)_7") (pintype "bidirectional"))
      (node (ref "Q3") (pin "2") (pinfunction "2_2") (pintype "passive"))
    )
    (net (code "42") (name "Net-(IC1-PB7(XTAL2{slash}TOSC2))") (class "Default")
      (node (ref "C16") (pin "2") (pinfunction "2_2") (pintype "passive"))
      (node (ref "IC1") (pin "8") (pinfunction "PB7(XTAL2/TOSC2)_8") (pintype "bidirectional"))
      (node (ref "Q3") (pin "1") (pinfunction "1_1") (pintype "passive"))
    )
    (net (code "43") (name "Net-(IC2-LEDA)") (class "Default")
      (node (ref "IC2") (pin "27") (pinfunction "LEDA_27") (pintype "output"))
      (node (ref "R15") (pin "2") (pinfunction "2_2") (pintype "passive"))
    )
    (net (code "44") (name "Net-(IC2-LEDB)") (class "Default")
      (node (ref "IC2") (pin "26") (pinfunction "LEDB_26") (pintype "output"))
      (node (ref "R16") (pin "2") (pinfunction "2_2") (pintype "passive"))
    )
    (net (code "45") (name "Net-(IC2-OSC1)") (class "Default")
      (node (ref "C7") (pin "1") (pinfunction "1_1") (pintype "passive"))
      (node (ref "IC2") (pin "23") (pinfunction "OSC1_23") (pintype "input"))
      (node (ref "Q4") (pin "2") (pinfunction "2_2") (pintype "passive"))
    )
    (net (code "46") (name "Net-(IC2-OSC2)") (class "Default")
      (node (ref "C13") (pin "2") (pinfunction "2_2") (pintype "passive"))
      (node (ref "IC2") (pin "24") (pinfunction "OSC2_24") (pintype "output"))
      (node (ref "Q4") (pin "1") (pinfunction "1_1") (pintype "passive"))
    )
    (net (code "47") (name "Net-(IC2-RBIAS)") (class "Default")
      (node (ref "IC2") (pin "14") (pinfunction "RBIAS_14") (pintype "passive"))
      (node (ref "R14") (pin "2") (pinfunction "2_2") (pintype "passive"))
    )
    (net (code "48") (name "Net-(IC2-VCAP)") (class "Default")
      (node (ref "C9") (pin "+") (pinfunction "+_+") (pintype "passive"))
      (node (ref "IC2") (pin "1") (pinfunction "VCAP_1") (pintype "power_in"))
    )
    (net (code "49") (name "Net-(IC4-IN)") (class "Default")
      (node (ref "C1") (pin "1") (pinfunction "1_1") (pintype "passive"))
      (node (ref "D1") (pin "C") (pinfunction "C_C") (pintype "passive"))
      (node (ref "IC4") (pin "3") (pinfunction "IN_3") (pintype "input"))
    )
    (net (code "50") (name "Net-(IC4-OUT)") (class "Default")
      (node (ref "C2") (pin "1") (pinfunction "1_1") (pintype "passive"))
      (node (ref "IC4") (pin "2") (pinfunction "OUT_2") (pintype "passive"))
      (node (ref "SJ3") (pin "1") (pinfunction "1_1") (pintype "passive"))
    )
    (net (code "51") (name "Net-(IC5-OUT)") (class "Default")
      (node (ref "C4") (pin "1") (pinfunction "1_1") (pintype "passive"))
      (node (ref "IC5") (pin "2") (pinfunction "OUT_2") (pintype "passive"))
      (node (ref "SJ2") (pin "1") (pinfunction "1_1") (pintype "passive"))
    )
    (net (code "52") (name "Net-(IC7-1Y)") (class "Default")
      (node (ref "IC7") (pin "2") (pinfunction "1Y_2") (pintype "bidirectional"))
      (node (ref "IC8") (pin "2") (pinfunction "CD/DAT3(~{CS})_2") (pintype "bidirectional"))
    )
    (net (code "53") (name "Net-(IC7-2Y)") (class "Default")
      (node (ref "IC7") (pin "4") (pinfunction "2Y_4") (pintype "bidirectional"))
      (node (ref "IC8") (pin "3") (pinfunction "CMD(DI)_3") (pintype "bidirectional"))
    )
    (net (code "54") (name "Net-(IC7-3Y)") (class "Default")
      (node (ref "IC7") (pin "6") (pinfunction "3Y_6") (pintype "bidirectional"))
      (node (ref "IC8") (pin "5") (pinfunction "CLK(SCLK)_5") (pintype "bidirectional"))
    )
    (net (code "55") (name "Net-(Q1-PadG)") (class "Default")
      (node (ref "Q1") (pin "G") (pinfunction "G_G") (pintype "passive"))
      (node (ref "R3") (pin "1") (pinfunction "1_1") (pintype "passive"))
      (node (ref "R4") (pin "1") (pinfunction "1_1") (pintype "passive"))
    )
    (net (code "56") (name "Net-(Q2-PadG)") (class "Default")
      (node (ref "Q2") (pin "G") (pinfunction "G_G") (pintype "passive"))
      (node (ref "R5") (pin "1") (pinfunction "1_1") (pintype "passive"))
      (node (ref "R6") (pin "1") (pinfunction "1_1") (pintype "passive"))
    )
    (net (code "57") (name "Net-(R7-Pad1)") (class "Default")
      (node (ref "R7") (pin "1") (pinfunction "1_1") (pintype "passive"))
      (node (ref "T1") (pin "B") (pinfunction "B_B") (pintype "passive"))
    )
    (net (code "58") (name "Net-(SG1-2)") (class "Default")
      (node (ref "SG1") (pin "-") (pinfunction "2_-") (pintype "passive"))
      (node (ref "T1") (pin "C") (pinfunction "C_C") (pintype "passive"))
    )
    (net (code "59") (name "Net-(X9A-KL)") (class "Default")
      (node (ref "D1") (pin "A") (pinfunction "A_A") (pintype "passive"))
      (node (ref "X9") (pin "1") (pinfunction "KL_1") (pintype "passive"))
    )
    (net (code "60") (name "Net-(X10D-KL)") (class "Default")
      (node (ref "Q1") (pin "D") (pinfunction "D_D") (pintype "passive"))
      (node (ref "X10") (pin "4") (pinfunction "KL_4") (pintype "passive"))
    )
    (net (code "61") (name "Net-(X10F-KL)") (class "Default")
      (node (ref "Q2") (pin "D") (pinfunction "D_D") (pintype "passive"))
      (node (ref "X10") (pin "6") (pinfunction "KL_6") (pintype "passive"))
    )
    (net (code "62") (name "VDD") (class "Default")
      (node (ref "JP4") (pin "2") (pinfunction "2_2") (pintype "passive"))
      (node (ref "X10") (pin "1") (pinfunction "KL_1") (pintype "passive"))
      (node (ref "X10") (pin "3") (pinfunction "KL_3") (pintype "passive"))
      (node (ref "X10") (pin "5") (pinfunction "KL_5") (pintype "passive"))
    )
    (net (code "63") (name "unconnected-(IC1-AREF-Pad20)") (class "Default")
      (node (ref "IC1") (pin "20") (pinfunction "AREF_20") (pintype "bidirectional"))
    )
    (net (code "64") (name "unconnected-(IC2-CLKOUT-Pad3)") (class "Default")
      (node (ref "IC2") (pin "3") (pinfunction "CLKOUT_3") (pintype "output"))
    )
    (net (code "65") (name "unconnected-(IC2-INT-Pad4)") (class "Default")
      (node (ref "IC2") (pin "4") (pinfunction "INT_4") (pintype "output"))
    )
    (net (code "66") (name "unconnected-(IC2-WOL-Pad5)") (class "Default")
      (node (ref "IC2") (pin "5") (pinfunction "WOL_5") (pintype "output"))
    )
    (net (code "67") (name "unconnected-(IC3-32KHZ-Pad1)") (class "Default")
      (node (ref "IC3") (pin "1") (pinfunction "32KHZ_1") (pintype "bidirectional"))
    )
    (net (code "68") (name "unconnected-(IC3-NC-Pad5)") (class "Default")
      (node (ref "IC3") (pin "5") (pinfunction "NC_5") (pintype "bidirectional"))
    )
    (net (code "69") (name "unconnected-(IC3-NC-Pad6)") (class "Default")
      (node (ref "IC3") (pin "6") (pinfunction "NC_6") (pintype "bidirectional"))
    )
    (net (code "70") (name "unconnected-(IC3-NC-Pad7)") (class "Default")
      (node (ref "IC3") (pin "7") (pinfunction "NC_7") (pintype "bidirectional"))
    )
    (net (code "71") (name "unconnected-(IC3-NC-Pad8)") (class "Default")
      (node (ref "IC3") (pin "8") (pinfunction "NC_8") (pintype "bidirectional"))
    )
    (net (code "72") (name "unconnected-(IC3-NC-Pad9)") (class "Default")
      (node (ref "IC3") (pin "9") (pinfunction "NC_9") (pintype "bidirectional"))
    )
    (net (code "73") (name "unconnected-(IC3-NC-Pad10)") (class "Default")
      (node (ref "IC3") (pin "10") (pinfunction "NC_10") (pintype "bidirectional"))
    )
    (net (code "74") (name "unconnected-(IC3-NC-Pad11)") (class "Default")
      (node (ref "IC3") (pin "11") (pinfunction "NC_11") (pintype "bidirectional"))
    )
    (net (code "75") (name "unconnected-(IC3-NC-Pad12)") (class "Default")
      (node (ref "IC3") (pin "12") (pinfunction "NC_12") (pintype "bidirectional"))
    )
    (net (code "76") (name "unconnected-(IC3-~{INT}-Pad3)") (class "Default")
      (node (ref "IC3") (pin "3") (pinfunction "~{INT}_3") (pintype "bidirectional"))
    )
    (net (code "77") (name "unconnected-(IC3-~{RST}-Pad4)") (class "Default")
      (node (ref "IC3") (pin "4") (pinfunction "~{RST}_4") (pintype "bidirectional"))
    )
    (net (code "78") (name "unconnected-(IC6-N.C.-Pad3)") (class "Default")
      (node (ref "IC6") (pin "3") (pinfunction "N.C._3") (pintype "passive"))
    )
    (net (code "79") (name "unconnected-(IC7-4Y-Pad10)") (class "Default")
      (node (ref "IC7") (pin "10") (pinfunction "4Y_10") (pintype "bidirectional"))
    )
    (net (code "80") (name "unconnected-(IC7-5Y-Pad12)") (class "Default")
      (node (ref "IC7") (pin "12") (pinfunction "5Y_12") (pintype "bidirectional"))
    )
    (net (code "81") (name "unconnected-(IC7-6Y-Pad15)") (class "Default")
      (node (ref "IC7") (pin "15") (pinfunction "6Y_15") (pintype "bidirectional"))
    )
    (net (code "82") (name "unconnected-(IC8-DAT1-Pad8)") (class "Default")
      (node (ref "IC8") (pin "8") (pinfunction "DAT1_8") (pintype "bidirectional"))
    )
    (net (code "83") (name "unconnected-(IC8-DAT2-Pad1)") (class "Default")
      (node (ref "IC8") (pin "1") (pinfunction "DAT2_1") (pintype "bidirectional"))
    )
    (net (code "84") (name "unconnected-(JP1-Pad3)") (class "Default")
      (node (ref "JP1") (pin "3") (pinfunction "3_3") (pintype "passive"))
    )
    (net (code "85") (name "unconnected-(JP2-Pad3)") (class "Default")
      (node (ref "JP2") (pin "3") (pinfunction "3_3") (pintype "passive"))
    )
    (net (code "86") (name "unconnected-(JP3-Pad3)") (class "Default")
      (node (ref "JP3") (pin "3") (pinfunction "3_3") (pintype "passive"))
    )
    (net (code "87") (name "unconnected-(JP5-Pad5)") (class "Default")
      (node (ref "JP5") (pin "5") (pinfunction "5_5") (pintype "passive"))
    )
    (net (code "88") (name "unconnected-(U$1-PadNC)") (class "Default")
      (node (ref "U$1") (pin "NC") (pinfunction "NC_NC") (pintype "bidirectional"))
    )
  )
)
